# IgorBrain.net
KiCad netlist of a schematic drawn in EAGLE
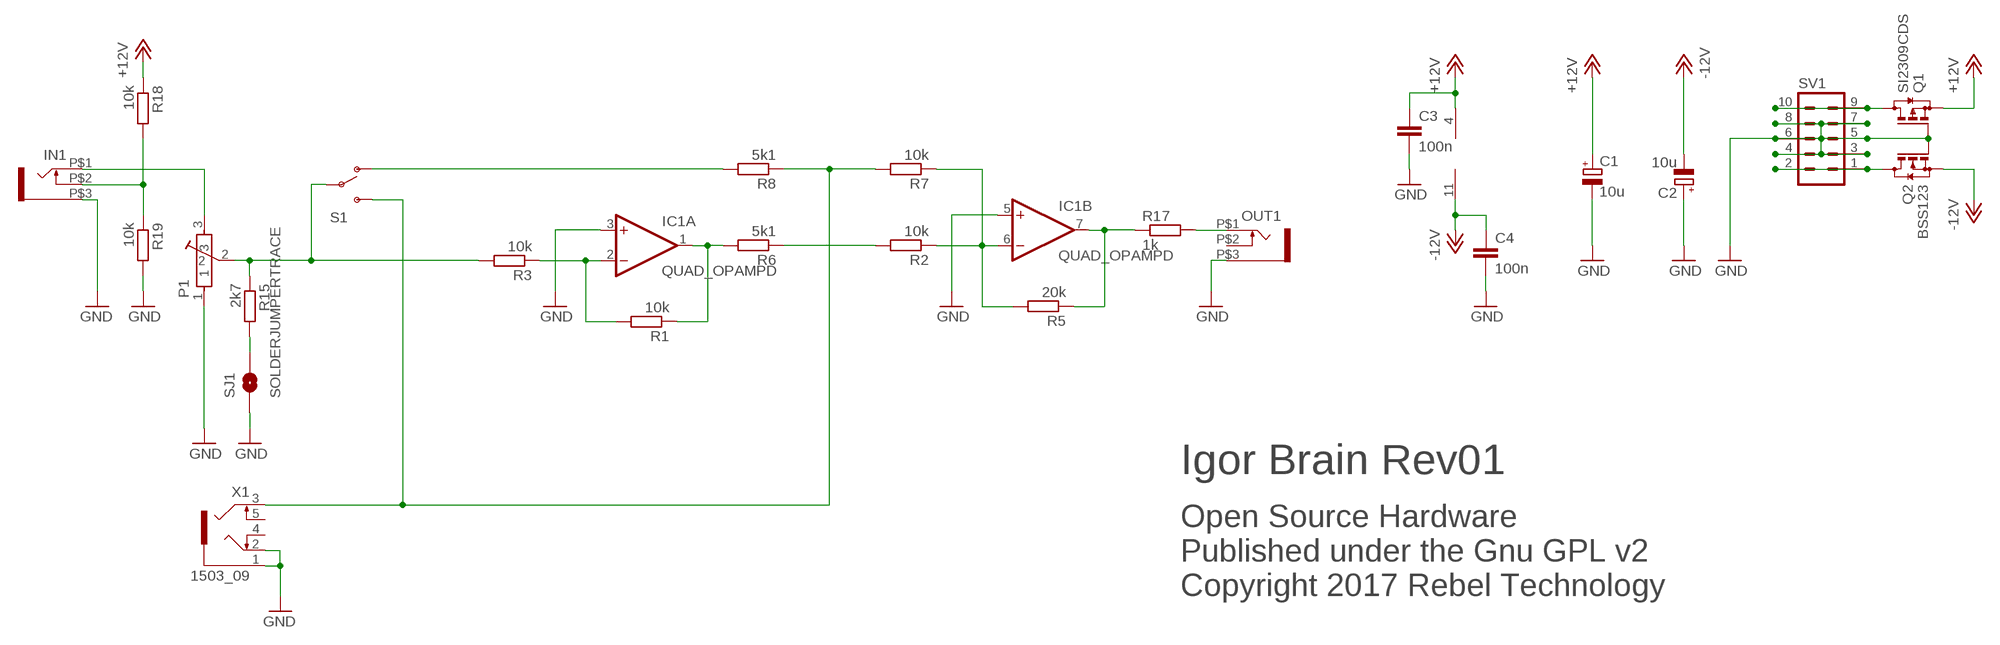
[diagram p0: schematic, sheet 1]

(export (version "E")
  (design (tool "Eeschema 10.0.6"))
  (components
    (comp (ref "C1")
      (value "10u")
      (footprint "eagle-import:153CLV-0505")
      (libsource (lib "eagle-import") (part "CPOL-EU153CLV-0505"))
    )
    (comp (ref "C2")
      (value "10u")
      (footprint "eagle-import:153CLV-0505")
      (libsource (lib "eagle-import") (part "CPOL-EU153CLV-0505"))
    )
    (comp (ref "C3")
      (value "100n")
      (footprint "eagle-import:C0603")
      (libsource (lib "eagle-import") (part "C-EUC0603"))
    )
    (comp (ref "C4")
      (value "100n")
      (footprint "eagle-import:C0603")
      (libsource (lib "eagle-import") (part "C-EUC0603"))
    )
    (comp (ref "IC1")
      (value "QUAD_OPAMPD")
      (footprint "eagle-import:SO14")
      (libsource (lib "eagle-import") (part "QUAD_OPAMPD"))
    )
    (comp (ref "IN1")
      (value "JACK-UJ-3502-R")
      (footprint "eagle-import:UJ-3502-R")
      (libsource (lib "eagle-import") (part "JACK-UJ-3502-R"))
    )
    (comp (ref "OUT1")
      (value "JACK-UJ-3502-R")
      (footprint "eagle-import:UJ-3502-R")
      (libsource (lib "eagle-import") (part "JACK-UJ-3502-R"))
    )
    (comp (ref "P1")
      (value "10k lin")
      (footprint "eagle-import:POT-BOURNS-PTD901")
      (libsource (lib "eagle-import") (part "POT-BOURNS-PTD901"))
    )
    (comp (ref "Q1")
      (value "SI2309CDS")
      (footprint "eagle-import:SOT23")
      (libsource (lib "eagle-import") (part "BSS84"))
    )
    (comp (ref "Q2")
      (value "BSS123")
      (footprint "eagle-import:SOT23")
      (libsource (lib "eagle-import") (part "BSS123"))
    )
    (comp (ref "R1")
      (value "10k")
      (footprint "eagle-import:0603")
      (libsource (lib "eagle-import") (part "R-EU_0603"))
    )
    (comp (ref "R2")
      (value "10k")
      (footprint "eagle-import:0603")
      (libsource (lib "eagle-import") (part "R-EU_0603"))
    )
    (comp (ref "R3")
      (value "10k")
      (footprint "eagle-import:0603")
      (libsource (lib "eagle-import") (part "R-EU_0603"))
    )
    (comp (ref "R5")
      (value "20k")
      (footprint "eagle-import:0603")
      (libsource (lib "eagle-import") (part "R-EU_0603"))
    )
    (comp (ref "R6")
      (value "5k1")
      (footprint "eagle-import:0603")
      (libsource (lib "eagle-import") (part "R-EU_0603"))
    )
    (comp (ref "R7")
      (value "10k")
      (footprint "eagle-import:0603")
      (libsource (lib "eagle-import") (part "R-EU_0603"))
    )
    (comp (ref "R8")
      (value "5k1")
      (footprint "eagle-import:0603")
      (libsource (lib "eagle-import") (part "R-EU_0603"))
    )
    (comp (ref "R15")
      (value "2k7")
      (footprint "eagle-import:0603")
      (libsource (lib "eagle-import") (part "R-EU_0603"))
    )
    (comp (ref "R17")
      (value "1k")
      (footprint "eagle-import:0603")
      (libsource (lib "eagle-import") (part "R-EU_0603"))
    )
    (comp (ref "R18")
      (value "10k")
      (footprint "eagle-import:0603")
      (libsource (lib "eagle-import") (part "R-EU_0603"))
    )
    (comp (ref "R19")
      (value "10k")
      (footprint "eagle-import:0603")
      (libsource (lib "eagle-import") (part "R-EU_0603"))
    )
    (comp (ref "S1")
      (value "SWITCH-SPST")
      (footprint "eagle-import:SWITCH-SPDT-SALECOM-T8014")
      (libsource (lib "eagle-import") (part "SWITCH-SPST"))
    )
    (comp (ref "SJ1")
      (value "SOLDERJUMPERTRACE")
      (footprint "eagle-import:SJ_2S-TRACE")
      (libsource (lib "eagle-import") (part "SOLDERJUMPERTRACE"))
    )
    (comp (ref "SV1")
      (value "MA05-2")
      (footprint "eagle-import:MA05-2")
      (libsource (lib "eagle-import") (part "MA05-2"))
    )
    (comp (ref "X1")
      (value "1503_09")
      (footprint "eagle-import:1503_09")
      (libsource (lib "eagle-import") (part "1503_09"))
    )
  )
  (nets
    (net (code "1") (name "+12V") (class "Default")
      (node (ref "C1") (pin "+") (pinfunction "+_+") (pintype "passive"))
      (node (ref "C3") (pin "1") (pinfunction "1_1") (pintype "passive"))
      (node (ref "IC1") (pin "4") (pinfunction "V+_4") (pintype "power_in"))
      (node (ref "Q1") (pin "2") (pinfunction "S_2") (pintype "passive"))
      (node (ref "R18") (pin "1") (pinfunction "1_1") (pintype "passive"))
    )
    (net (code "2") (name "-12V") (class "Default")
      (node (ref "C2") (pin "-") (pinfunction "-_-") (pintype "passive"))
      (node (ref "C4") (pin "1") (pinfunction "1_1") (pintype "passive"))
      (node (ref "IC1") (pin "11") (pinfunction "V-_11") (pintype "power_in"))
      (node (ref "Q2") (pin "2") (pinfunction "S_2") (pintype "passive"))
    )
    (net (code "3") (name "GND") (class "Default")
      (node (ref "C1") (pin "-") (pinfunction "-_-") (pintype "passive"))
      (node (ref "C2") (pin "+") (pinfunction "+_+") (pintype "passive"))
      (node (ref "C3") (pin "2") (pinfunction "2_2") (pintype "passive"))
      (node (ref "C4") (pin "2") (pinfunction "2_2") (pintype "passive"))
      (node (ref "IC1") (pin "3") (pinfunction "+IN_3") (pintype "input"))
      (node (ref "IC1") (pin "5") (pinfunction "+IN_5") (pintype "input"))
      (node (ref "IN1") (pin "P$3") (pinfunction "SLEEVE_P$3") (pintype "passive"))
      (node (ref "OUT1") (pin "P$3") (pinfunction "SLEEVE_P$3") (pintype "passive"))
      (node (ref "P1") (pin "1") (pinfunction "1_1") (pintype "bidirectional"))
      (node (ref "Q1") (pin "1") (pinfunction "G_1") (pintype "passive"))
      (node (ref "Q2") (pin "1") (pinfunction "G_1") (pintype "passive"))
      (node (ref "R19") (pin "2") (pinfunction "2_2") (pintype "passive"))
      (node (ref "SJ1") (pin "1") (pinfunction "1_1") (pintype "passive"))
      (node (ref "SV1") (pin "3") (pinfunction "3_3") (pintype "passive"))
      (node (ref "SV1") (pin "4") (pinfunction "4_4") (pintype "passive"))
      (node (ref "SV1") (pin "5") (pinfunction "5_5") (pintype "passive"))
      (node (ref "SV1") (pin "6") (pinfunction "6_6") (pintype "passive"))
      (node (ref "SV1") (pin "7") (pinfunction "7_7") (pintype "passive"))
      (node (ref "SV1") (pin "8") (pinfunction "8_8") (pintype "passive"))
      (node (ref "X1") (pin "1") (pinfunction "1_1") (pintype "passive"))
      (node (ref "X1") (pin "2") (pinfunction "2_2") (pintype "passive"))
    )
    (net (code "4") (name "Net-(IC1A--IN)") (class "Default")
      (node (ref "IC1") (pin "2") (pinfunction "-IN_2") (pintype "input"))
      (node (ref "R1") (pin "2") (pinfunction "2_2") (pintype "passive"))
      (node (ref "R3") (pin "1") (pinfunction "1_1") (pintype "passive"))
    )
    (net (code "5") (name "Net-(IC1A-OUT)") (class "Default")
      (node (ref "IC1") (pin "1") (pinfunction "OUT_1") (pintype "output"))
      (node (ref "R1") (pin "1") (pinfunction "1_1") (pintype "passive"))
      (node (ref "R6") (pin "2") (pinfunction "2_2") (pintype "passive"))
    )
    (net (code "6") (name "Net-(IC1B--IN)") (class "Default")
      (node (ref "IC1") (pin "6") (pinfunction "-IN_6") (pintype "input"))
      (node (ref "R2") (pin "1") (pinfunction "1_1") (pintype "passive"))
      (node (ref "R5") (pin "2") (pinfunction "2_2") (pintype "passive"))
      (node (ref "R7") (pin "1") (pinfunction "1_1") (pintype "passive"))
    )
    (net (code "7") (name "Net-(IC1B-OUT)") (class "Default")
      (node (ref "IC1") (pin "7") (pinfunction "OUT_7") (pintype "output"))
      (node (ref "R17") (pin "1") (pinfunction "1_1") (pintype "passive"))
      (node (ref "R5") (pin "1") (pinfunction "1_1") (pintype "passive"))
    )
    (net (code "8") (name "Net-(IN1-SW)") (class "Default")
      (node (ref "IN1") (pin "P$2") (pinfunction "SW_P$2") (pintype "passive"))
      (node (ref "R18") (pin "2") (pinfunction "2_2") (pintype "passive"))
      (node (ref "R19") (pin "1") (pinfunction "1_1") (pintype "passive"))
    )
    (net (code "9") (name "Net-(IN1-TIP)") (class "Default")
      (node (ref "IN1") (pin "P$1") (pinfunction "TIP_P$1") (pintype "passive"))
      (node (ref "P1") (pin "3") (pinfunction "3_3") (pintype "bidirectional"))
    )
    (net (code "10") (name "Net-(OUT1-TIP)") (class "Default")
      (node (ref "OUT1") (pin "P$1") (pinfunction "TIP_P$1") (pintype "passive"))
      (node (ref "R17") (pin "2") (pinfunction "2_2") (pintype "passive"))
    )
    (net (code "11") (name "Net-(Q1-D)") (class "Default")
      (node (ref "Q1") (pin "3") (pinfunction "D_3") (pintype "passive"))
      (node (ref "SV1") (pin "10") (pinfunction "10_10") (pintype "passive"))
      (node (ref "SV1") (pin "9") (pinfunction "9_9") (pintype "passive"))
    )
    (net (code "12") (name "Net-(Q2-D)") (class "Default")
      (node (ref "Q2") (pin "3") (pinfunction "D_3") (pintype "passive"))
      (node (ref "SV1") (pin "1") (pinfunction "1_1") (pintype "passive"))
      (node (ref "SV1") (pin "2") (pinfunction "2_2") (pintype "passive"))
    )
    (net (code "13") (name "Net-(R2-Pad2)") (class "Default")
      (node (ref "R2") (pin "2") (pinfunction "2_2") (pintype "passive"))
      (node (ref "R6") (pin "1") (pinfunction "1_1") (pintype "passive"))
    )
    (net (code "14") (name "Net-(R15-Pad2)") (class "Default")
      (node (ref "R15") (pin "2") (pinfunction "2_2") (pintype "passive"))
      (node (ref "SJ1") (pin "2") (pinfunction "2_2") (pintype "passive"))
    )
    (net (code "15") (name "Net-(S1-O)") (class "Default")
      (node (ref "R8") (pin "2") (pinfunction "2_2") (pintype "passive"))
      (node (ref "S1") (pin "1") (pinfunction "O_1") (pintype "passive"))
    )
    (net (code "16") (name "Net-(S1-P)") (class "Default")
      (node (ref "P1") (pin "2") (pinfunction "2_2") (pintype "bidirectional"))
      (node (ref "R15") (pin "1") (pinfunction "1_1") (pintype "passive"))
      (node (ref "R3") (pin "2") (pinfunction "2_2") (pintype "passive"))
      (node (ref "S1") (pin "2") (pinfunction "P_2") (pintype "passive"))
    )
    (net (code "17") (name "Net-(S1-S)") (class "Default")
      (node (ref "R7") (pin "2") (pinfunction "2_2") (pintype "passive"))
      (node (ref "R8") (pin "1") (pinfunction "1_1") (pintype "passive"))
      (node (ref "S1") (pin "3") (pinfunction "S_3") (pintype "passive"))
      (node (ref "X1") (pin "3") (pinfunction "3_3") (pintype "passive"))
    )
    (net (code "18") (name "unconnected-(OUT1-SW-PadP$2)") (class "Default")
      (node (ref "OUT1") (pin "P$2") (pinfunction "SW_P$2") (pintype "passive"))
    )
    (net (code "19") (name "unconnected-(X1-Pad4)") (class "Default")
      (node (ref "X1") (pin "4") (pinfunction "4_4") (pintype "passive"))
    )
    (net (code "20") (name "unconnected-(X1-Pad5)") (class "Default")
      (node (ref "X1") (pin "5") (pinfunction "5_5") (pintype "passive"))
    )
  )
)
